# schematic.net
KiCad netlist of a schematic drawn in Altium Designer
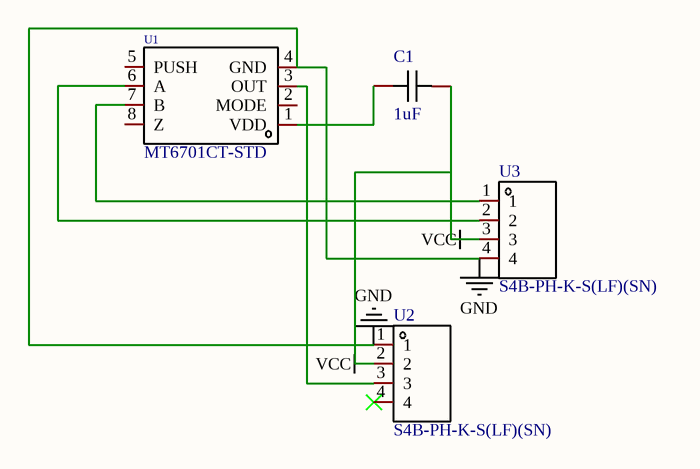
[diagram p0: schematic.schdoc]

(export (version "E")
  (design (tool "Eeschema 10.0.6"))
  (components
    (comp (ref "C1")
      (value "1uF")
      (fields (field (name "NAME") "1uF"))
      (libsource (lib "altium-import") (part "root_2_CAP_0603_"))
    )
    (comp (ref "U1")
      (value "MT6701CT-STD")
      (fields (field (name "NAME") "MT6701CT-STD") (field (name "MANUFACTURER") "MagnTek(麦歌恩)"))
      (libsource (lib "altium-import") (part "root_2_MT6701CT-STD_"))
    )
    (comp (ref "U2")
      (value "S4B-PH-K-S(LF)(SN)")
      (fields (field (name "NAME") "S4B-PH-K-S(LF)(SN)") (field (name "MANUFACTURER") "JST"))
      (libsource (lib "altium-import") (part "root_0_S4B-PH-K-S(LF)(SN)_"))
    )
    (comp (ref "U3")
      (value "S4B-PH-K-S(LF)(SN)")
      (fields (field (name "NAME") "S4B-PH-K-S(LF)(SN)") (field (name "MANUFACTURER") "JST"))
      (libsource (lib "altium-import") (part "root_0_S4B-PH-K-S(LF)(SN)_"))
    )
  )
  (nets
    (net (code "1") (name "GND") (class "Default")
      (node (ref "U1") (pin "4") (pinfunction "GND_4") (pintype "passive"))
      (node (ref "U2") (pin "1") (pinfunction "1_1") (pintype "passive"))
      (node (ref "U3") (pin "4") (pinfunction "4_4") (pintype "passive"))
    )
    (net (code "2") (name "Net-(U1-A)") (class "Default")
      (node (ref "U1") (pin "6") (pinfunction "A_6") (pintype "passive"))
      (node (ref "U3") (pin "2") (pinfunction "2_2") (pintype "passive"))
    )
    (net (code "3") (name "Net-(U1-B)") (class "Default")
      (node (ref "U1") (pin "7") (pinfunction "B_7") (pintype "passive"))
      (node (ref "U3") (pin "1") (pinfunction "1_1") (pintype "passive"))
    )
    (net (code "4") (name "Net-(U1-OUT)") (class "Default")
      (node (ref "U1") (pin "3") (pinfunction "OUT_3") (pintype "passive"))
      (node (ref "U2") (pin "3") (pinfunction "3_3") (pintype "passive"))
    )
    (net (code "5") (name "Net-(U1-VDD)") (class "Default")
      (node (ref "C1") (pin "1") (pinfunction "1_1") (pintype "passive"))
      (node (ref "U1") (pin "1") (pinfunction "VDD_1") (pintype "passive"))
    )
    (net (code "6") (name "VCC") (class "Default")
      (node (ref "C1") (pin "2") (pinfunction "2_2") (pintype "passive"))
      (node (ref "U2") (pin "2") (pinfunction "2_2") (pintype "passive"))
      (node (ref "U3") (pin "3") (pinfunction "3_3") (pintype "passive"))
    )
    (net (code "7") (name "unconnected-(U1-MODE-Pad2)") (class "Default")
      (node (ref "U1") (pin "2") (pinfunction "MODE_2") (pintype "passive"))
    )
    (net (code "8") (name "unconnected-(U1-PUSH-Pad5)") (class "Default")
      (node (ref "U1") (pin "5") (pinfunction "PUSH_5") (pintype "passive"))
    )
    (net (code "9") (name "unconnected-(U1-Z-Pad8)") (class "Default")
      (node (ref "U1") (pin "8") (pinfunction "Z_8") (pintype "passive"))
    )
    (net (code "10") (name "unconnected-(U2-Pad4)") (class "Default")
      (node (ref "U2") (pin "4") (pinfunction "4_4") (pintype "passive+no_connect"))
    )
  )
)
